# Arduino.net
KiCad netlist of a schematic drawn in Altium Designer
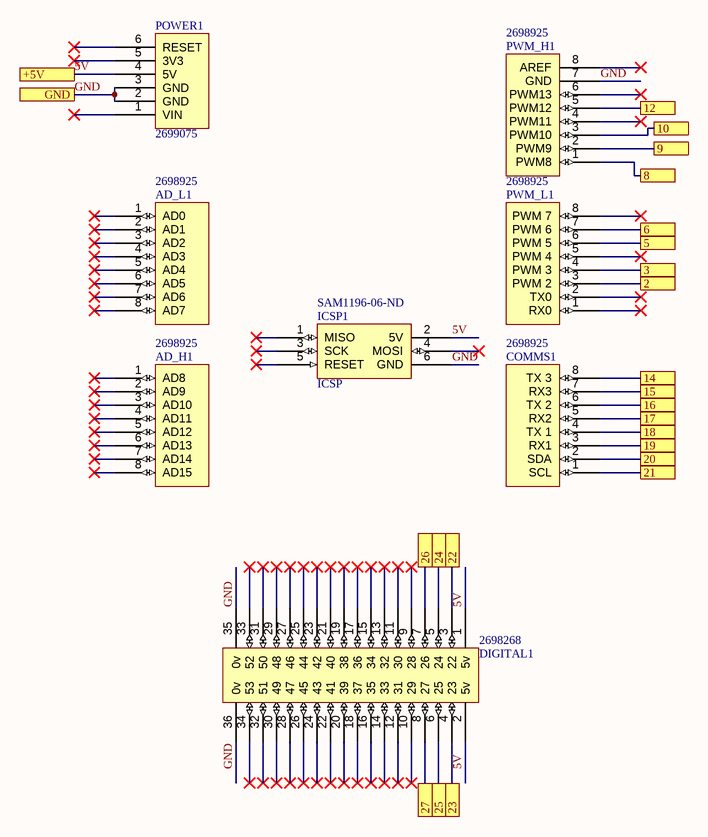
[diagram p0: Arduino.SchDoc]

(export (version "E")
  (design (tool "Eeschema 10.0.6"))
  (components
    (comp (ref "AD_H1")
      (value "AD_H")
      (footprint "Header 8x1 8.5mm")
      (fields (field (name "SUPPLIER PART NUMBER 4") "2698925"))
      (libsource (lib "Header") (part "AD_H"))
    )
    (comp (ref "AD_L1")
      (value "AD_L")
      (footprint "Header 8x1 8.5mm")
      (fields (field (name "SUPPLIER PART NUMBER 5") "2698925"))
      (libsource (lib "Header") (part "AD_L"))
    )
    (comp (ref "COMMS1")
      (value "Communication")
      (footprint "Header 8x1 8.5mm")
      (fields (field (name "SUPPLIER PART NUMBER 4") "2698925"))
      (libsource (lib "Header") (part "Communication"))
    )
    (comp (ref "DIGITAL1")
      (value "IO_36")
      (footprint "HEADER 36X 8MM")
      (fields (field (name "SUPPLIER PART NUMBER 5") "2698268"))
      (libsource (lib "Header") (part "IO_36"))
    )
    (comp (ref "ICSP1")
      (value "ICSP")
      (footprint "ICSP")
      (fields (field (name "SUPPLIER PART NUMBER 5") "SAM1196-06-ND"))
      (libsource (lib "Header") (part "ICSP"))
    )
    (comp (ref "POWER1")
      (value "POWER")
      (footprint "Header 6x1 8.5mm")
      (fields (field (name "SUPPLIER PART NUMBER 2") "2699075"))
      (libsource (lib "Header") (part "POWER"))
    )
    (comp (ref "PWM_H1")
      (value "PWM_H")
      (footprint "Header 8x1 8.5mm")
      (fields (field (name "SUPPLIER PART NUMBER 4") "2698925"))
      (libsource (lib "Header") (part "PWM_H"))
    )
    (comp (ref "PWM_L1")
      (value "PWM_L")
      (footprint "Header 8x1 8.5mm")
      (fields (field (name "SUPPLIER PART NUMBER 4") "2698925"))
      (libsource (lib "Header") (part "PWM_L"))
    )
  )
  (nets
    (net (code "1") (name "/2") (class "Default")
      (node (ref "PWM_L1") (pin "3") (pinfunction "PWM_2_3") (pintype "bidirectional"))
    )
    (net (code "2") (name "/3") (class "Default")
      (node (ref "PWM_L1") (pin "4") (pinfunction "PWM_3_4") (pintype "bidirectional"))
    )
    (net (code "3") (name "/5") (class "Default")
      (node (ref "PWM_L1") (pin "6") (pinfunction "PWM_5_6") (pintype "bidirectional"))
    )
    (net (code "4") (name "/5V") (class "Default")
      (node (ref "DIGITAL1") (pin "1") (pinfunction "5v_1") (pintype "power_in"))
      (node (ref "DIGITAL1") (pin "2") (pinfunction "5v_2") (pintype "power_in"))
      (node (ref "ICSP1") (pin "2") (pinfunction "5V_2") (pintype "power_in"))
      (node (ref "POWER1") (pin "4") (pinfunction "5V_4") (pintype "power_in"))
    )
    (net (code "5") (name "/6") (class "Default")
      (node (ref "PWM_L1") (pin "7") (pinfunction "PWM_6_7") (pintype "bidirectional"))
    )
    (net (code "6") (name "/8") (class "Default")
      (node (ref "PWM_H1") (pin "1") (pinfunction "PWM8_1") (pintype "bidirectional"))
    )
    (net (code "7") (name "/9") (class "Default")
      (node (ref "PWM_H1") (pin "2") (pinfunction "PWM9_2") (pintype "bidirectional"))
    )
    (net (code "8") (name "/10") (class "Default")
      (node (ref "PWM_H1") (pin "3") (pinfunction "PWM10_3") (pintype "bidirectional"))
    )
    (net (code "9") (name "/12") (class "Default")
      (node (ref "PWM_H1") (pin "5") (pinfunction "PWM12_5") (pintype "bidirectional"))
    )
    (net (code "10") (name "/14") (class "Default")
      (node (ref "COMMS1") (pin "8") (pinfunction "TX_3_8") (pintype "bidirectional"))
    )
    (net (code "11") (name "/15") (class "Default")
      (node (ref "COMMS1") (pin "7") (pinfunction "RX3_7") (pintype "bidirectional"))
    )
    (net (code "12") (name "/16") (class "Default")
      (node (ref "COMMS1") (pin "6") (pinfunction "TX_2_6") (pintype "bidirectional"))
    )
    (net (code "13") (name "/17") (class "Default")
      (node (ref "COMMS1") (pin "5") (pinfunction "RX2_5") (pintype "bidirectional"))
    )
    (net (code "14") (name "/18") (class "Default")
      (node (ref "COMMS1") (pin "4") (pinfunction "TX_1_4") (pintype "bidirectional"))
    )
    (net (code "15") (name "/19") (class "Default")
      (node (ref "COMMS1") (pin "3") (pinfunction "RX1_3") (pintype "bidirectional"))
    )
    (net (code "16") (name "/20") (class "Default")
      (node (ref "COMMS1") (pin "2") (pinfunction "SDA_2") (pintype "bidirectional"))
    )
    (net (code "17") (name "/21") (class "Default")
      (node (ref "COMMS1") (pin "1") (pinfunction "SCL_1") (pintype "bidirectional"))
    )
    (net (code "18") (name "/22") (class "Default")
      (node (ref "DIGITAL1") (pin "3") (pinfunction "22_3") (pintype "bidirectional"))
    )
    (net (code "19") (name "/23") (class "Default")
      (node (ref "DIGITAL1") (pin "4") (pinfunction "23_4") (pintype "bidirectional"))
    )
    (net (code "20") (name "/24") (class "Default")
      (node (ref "DIGITAL1") (pin "5") (pinfunction "24_5") (pintype "bidirectional"))
    )
    (net (code "21") (name "/25") (class "Default")
      (node (ref "DIGITAL1") (pin "6") (pinfunction "25_6") (pintype "bidirectional"))
    )
    (net (code "22") (name "/26") (class "Default")
      (node (ref "DIGITAL1") (pin "7") (pinfunction "26_7") (pintype "bidirectional"))
    )
    (net (code "23") (name "/27") (class "Default")
      (node (ref "DIGITAL1") (pin "8") (pinfunction "27_8") (pintype "bidirectional"))
    )
    (net (code "24") (name "/GND") (class "Default")
      (node (ref "DIGITAL1") (pin "35") (pinfunction "0v_35") (pintype "power_in"))
      (node (ref "DIGITAL1") (pin "36") (pinfunction "0v_36") (pintype "power_in"))
      (node (ref "ICSP1") (pin "6") (pinfunction "GND_6") (pintype "power_in"))
      (node (ref "POWER1") (pin "2") (pinfunction "GND_2") (pintype "power_in"))
      (node (ref "POWER1") (pin "3") (pinfunction "GND_3") (pintype "power_in"))
      (node (ref "PWM_H1") (pin "7") (pinfunction "GND_7") (pintype "power_in"))
    )
    (net (code "25") (name "unconnected-(AD_H1-AD8-Pad1)") (class "Default")
      (node (ref "AD_H1") (pin "1") (pinfunction "AD8_1") (pintype "bidirectional+no_connect"))
    )
    (net (code "26") (name "unconnected-(AD_H1-AD9-Pad2)") (class "Default")
      (node (ref "AD_H1") (pin "2") (pinfunction "AD9_2") (pintype "bidirectional+no_connect"))
    )
    (net (code "27") (name "unconnected-(AD_H1-AD10-Pad3)") (class "Default")
      (node (ref "AD_H1") (pin "3") (pinfunction "AD10_3") (pintype "bidirectional+no_connect"))
    )
    (net (code "28") (name "unconnected-(AD_H1-AD11-Pad4)") (class "Default")
      (node (ref "AD_H1") (pin "4") (pinfunction "AD11_4") (pintype "bidirectional+no_connect"))
    )
    (net (code "29") (name "unconnected-(AD_H1-AD12-Pad5)") (class "Default")
      (node (ref "AD_H1") (pin "5") (pinfunction "AD12_5") (pintype "bidirectional+no_connect"))
    )
    (net (code "30") (name "unconnected-(AD_H1-AD13-Pad6)") (class "Default")
      (node (ref "AD_H1") (pin "6") (pinfunction "AD13_6") (pintype "bidirectional+no_connect"))
    )
    (net (code "31") (name "unconnected-(AD_H1-AD14-Pad7)") (class "Default")
      (node (ref "AD_H1") (pin "7") (pinfunction "AD14_7") (pintype "bidirectional+no_connect"))
    )
    (net (code "32") (name "unconnected-(AD_H1-AD15-Pad8)") (class "Default")
      (node (ref "AD_H1") (pin "8") (pinfunction "AD15_8") (pintype "bidirectional+no_connect"))
    )
    (net (code "33") (name "unconnected-(AD_L1-AD0-Pad1)") (class "Default")
      (node (ref "AD_L1") (pin "1") (pinfunction "AD0_1") (pintype "bidirectional+no_connect"))
    )
    (net (code "34") (name "unconnected-(AD_L1-AD1-Pad2)") (class "Default")
      (node (ref "AD_L1") (pin "2") (pinfunction "AD1_2") (pintype "bidirectional+no_connect"))
    )
    (net (code "35") (name "unconnected-(AD_L1-AD2-Pad3)") (class "Default")
      (node (ref "AD_L1") (pin "3") (pinfunction "AD2_3") (pintype "bidirectional+no_connect"))
    )
    (net (code "36") (name "unconnected-(AD_L1-AD3-Pad4)") (class "Default")
      (node (ref "AD_L1") (pin "4") (pinfunction "AD3_4") (pintype "bidirectional+no_connect"))
    )
    (net (code "37") (name "unconnected-(AD_L1-AD4-Pad5)") (class "Default")
      (node (ref "AD_L1") (pin "5") (pinfunction "AD4_5") (pintype "bidirectional+no_connect"))
    )
    (net (code "38") (name "unconnected-(AD_L1-AD5-Pad6)") (class "Default")
      (node (ref "AD_L1") (pin "6") (pinfunction "AD5_6") (pintype "bidirectional+no_connect"))
    )
    (net (code "39") (name "unconnected-(AD_L1-AD6-Pad7)") (class "Default")
      (node (ref "AD_L1") (pin "7") (pinfunction "AD6_7") (pintype "bidirectional+no_connect"))
    )
    (net (code "40") (name "unconnected-(AD_L1-AD7-Pad8)") (class "Default")
      (node (ref "AD_L1") (pin "8") (pinfunction "AD7_8") (pintype "bidirectional+no_connect"))
    )
    (net (code "41") (name "unconnected-(DIGITAL1-28-Pad9)") (class "Default")
      (node (ref "DIGITAL1") (pin "9") (pinfunction "28_9") (pintype "bidirectional+no_connect"))
    )
    (net (code "42") (name "unconnected-(DIGITAL1-29-Pad10)") (class "Default")
      (node (ref "DIGITAL1") (pin "10") (pinfunction "29_10") (pintype "bidirectional+no_connect"))
    )
    (net (code "43") (name "unconnected-(DIGITAL1-30-Pad11)") (class "Default")
      (node (ref "DIGITAL1") (pin "11") (pinfunction "30_11") (pintype "bidirectional+no_connect"))
    )
    (net (code "44") (name "unconnected-(DIGITAL1-31-Pad12)") (class "Default")
      (node (ref "DIGITAL1") (pin "12") (pinfunction "31_12") (pintype "bidirectional+no_connect"))
    )
    (net (code "45") (name "unconnected-(DIGITAL1-32-Pad13)") (class "Default")
      (node (ref "DIGITAL1") (pin "13") (pinfunction "32_13") (pintype "bidirectional+no_connect"))
    )
    (net (code "46") (name "unconnected-(DIGITAL1-33-Pad14)") (class "Default")
      (node (ref "DIGITAL1") (pin "14") (pinfunction "33_14") (pintype "bidirectional+no_connect"))
    )
    (net (code "47") (name "unconnected-(DIGITAL1-34-Pad15)") (class "Default")
      (node (ref "DIGITAL1") (pin "15") (pinfunction "34_15") (pintype "bidirectional+no_connect"))
    )
    (net (code "48") (name "unconnected-(DIGITAL1-35-Pad16)") (class "Default")
      (node (ref "DIGITAL1") (pin "16") (pinfunction "35_16") (pintype "bidirectional+no_connect"))
    )
    (net (code "49") (name "unconnected-(DIGITAL1-36-Pad17)") (class "Default")
      (node (ref "DIGITAL1") (pin "17") (pinfunction "36_17") (pintype "bidirectional+no_connect"))
    )
    (net (code "50") (name "unconnected-(DIGITAL1-37-Pad18)") (class "Default")
      (node (ref "DIGITAL1") (pin "18") (pinfunction "37_18") (pintype "bidirectional+no_connect"))
    )
    (net (code "51") (name "unconnected-(DIGITAL1-38-Pad19)") (class "Default")
      (node (ref "DIGITAL1") (pin "19") (pinfunction "38_19") (pintype "bidirectional+no_connect"))
    )
    (net (code "52") (name "unconnected-(DIGITAL1-39-Pad20)") (class "Default")
      (node (ref "DIGITAL1") (pin "20") (pinfunction "39_20") (pintype "bidirectional+no_connect"))
    )
    (net (code "53") (name "unconnected-(DIGITAL1-40-Pad21)") (class "Default")
      (node (ref "DIGITAL1") (pin "21") (pinfunction "40_21") (pintype "bidirectional+no_connect"))
    )
    (net (code "54") (name "unconnected-(DIGITAL1-41-Pad22)") (class "Default")
      (node (ref "DIGITAL1") (pin "22") (pinfunction "41_22") (pintype "bidirectional+no_connect"))
    )
    (net (code "55") (name "unconnected-(DIGITAL1-42-Pad23)") (class "Default")
      (node (ref "DIGITAL1") (pin "23") (pinfunction "42_23") (pintype "bidirectional+no_connect"))
    )
    (net (code "56") (name "unconnected-(DIGITAL1-43-Pad24)") (class "Default")
      (node (ref "DIGITAL1") (pin "24") (pinfunction "43_24") (pintype "bidirectional+no_connect"))
    )
    (net (code "57") (name "unconnected-(DIGITAL1-44-Pad25)") (class "Default")
      (node (ref "DIGITAL1") (pin "25") (pinfunction "44_25") (pintype "bidirectional+no_connect"))
    )
    (net (code "58") (name "unconnected-(DIGITAL1-45-Pad26)") (class "Default")
      (node (ref "DIGITAL1") (pin "26") (pinfunction "45_26") (pintype "bidirectional+no_connect"))
    )
    (net (code "59") (name "unconnected-(DIGITAL1-46-Pad27)") (class "Default")
      (node (ref "DIGITAL1") (pin "27") (pinfunction "46_27") (pintype "bidirectional+no_connect"))
    )
    (net (code "60") (name "unconnected-(DIGITAL1-47-Pad28)") (class "Default")
      (node (ref "DIGITAL1") (pin "28") (pinfunction "47_28") (pintype "bidirectional+no_connect"))
    )
    (net (code "61") (name "unconnected-(DIGITAL1-48-Pad29)") (class "Default")
      (node (ref "DIGITAL1") (pin "29") (pinfunction "48_29") (pintype "bidirectional+no_connect"))
    )
    (net (code "62") (name "unconnected-(DIGITAL1-49-Pad30)") (class "Default")
      (node (ref "DIGITAL1") (pin "30") (pinfunction "49_30") (pintype "bidirectional+no_connect"))
    )
    (net (code "63") (name "unconnected-(DIGITAL1-50-Pad31)") (class "Default")
      (node (ref "DIGITAL1") (pin "31") (pinfunction "50_31") (pintype "bidirectional+no_connect"))
    )
    (net (code "64") (name "unconnected-(DIGITAL1-51-Pad32)") (class "Default")
      (node (ref "DIGITAL1") (pin "32") (pinfunction "51_32") (pintype "bidirectional+no_connect"))
    )
    (net (code "65") (name "unconnected-(DIGITAL1-52-Pad33)") (class "Default")
      (node (ref "DIGITAL1") (pin "33") (pinfunction "52_33") (pintype "bidirectional+no_connect"))
    )
    (net (code "66") (name "unconnected-(DIGITAL1-53-Pad34)") (class "Default")
      (node (ref "DIGITAL1") (pin "34") (pinfunction "53_34") (pintype "bidirectional+no_connect"))
    )
    (net (code "67") (name "unconnected-(ICSP1-MISO-Pad1)") (class "Default")
      (node (ref "ICSP1") (pin "1") (pinfunction "MISO_1") (pintype "bidirectional+no_connect"))
    )
    (net (code "68") (name "unconnected-(ICSP1-MOSI-Pad4)") (class "Default")
      (node (ref "ICSP1") (pin "4") (pinfunction "MOSI_4") (pintype "bidirectional+no_connect"))
    )
    (net (code "69") (name "unconnected-(ICSP1-RESET-Pad5)") (class "Default")
      (node (ref "ICSP1") (pin "5") (pinfunction "RESET_5") (pintype "input+no_connect"))
    )
    (net (code "70") (name "unconnected-(ICSP1-SCK-Pad3)") (class "Default")
      (node (ref "ICSP1") (pin "3") (pinfunction "SCK_3") (pintype "bidirectional+no_connect"))
    )
    (net (code "71") (name "unconnected-(POWER1-3V3-Pad5)") (class "Default")
      (node (ref "POWER1") (pin "5") (pinfunction "3V3_5") (pintype "power_in+no_connect"))
    )
    (net (code "72") (name "unconnected-(POWER1-RESET-Pad6)") (class "Default")
      (node (ref "POWER1") (pin "6") (pinfunction "RESET_6") (pintype "passive+no_connect"))
    )
    (net (code "73") (name "unconnected-(POWER1-VIN-Pad1)") (class "Default")
      (node (ref "POWER1") (pin "1") (pinfunction "VIN_1") (pintype "power_in+no_connect"))
    )
    (net (code "74") (name "unconnected-(PWM_H1-AREF-Pad8)") (class "Default")
      (node (ref "PWM_H1") (pin "8") (pinfunction "AREF_8") (pintype "passive+no_connect"))
    )
    (net (code "75") (name "unconnected-(PWM_H1-PWM11-Pad4)") (class "Default")
      (node (ref "PWM_H1") (pin "4") (pinfunction "PWM11_4") (pintype "bidirectional+no_connect"))
    )
    (net (code "76") (name "unconnected-(PWM_H1-PWM13-Pad6)") (class "Default")
      (node (ref "PWM_H1") (pin "6") (pinfunction "PWM13_6") (pintype "bidirectional+no_connect"))
    )
    (net (code "77") (name "unconnected-(PWM_L1-PWM_4-Pad5)") (class "Default")
      (node (ref "PWM_L1") (pin "5") (pinfunction "PWM_4_5") (pintype "bidirectional+no_connect"))
    )
    (net (code "78") (name "unconnected-(PWM_L1-PWM_7-Pad8)") (class "Default")
      (node (ref "PWM_L1") (pin "8") (pinfunction "PWM_7_8") (pintype "bidirectional+no_connect"))
    )
    (net (code "79") (name "unconnected-(PWM_L1-RX0-Pad1)") (class "Default")
      (node (ref "PWM_L1") (pin "1") (pinfunction "RX0_1") (pintype "bidirectional+no_connect"))
    )
    (net (code "80") (name "unconnected-(PWM_L1-TX0-Pad2)") (class "Default")
      (node (ref "PWM_L1") (pin "2") (pinfunction "TX0_2") (pintype "bidirectional+no_connect"))
    )
  )
)
